# untitled.net
KiCad netlist of a schematic drawn in EAGLE
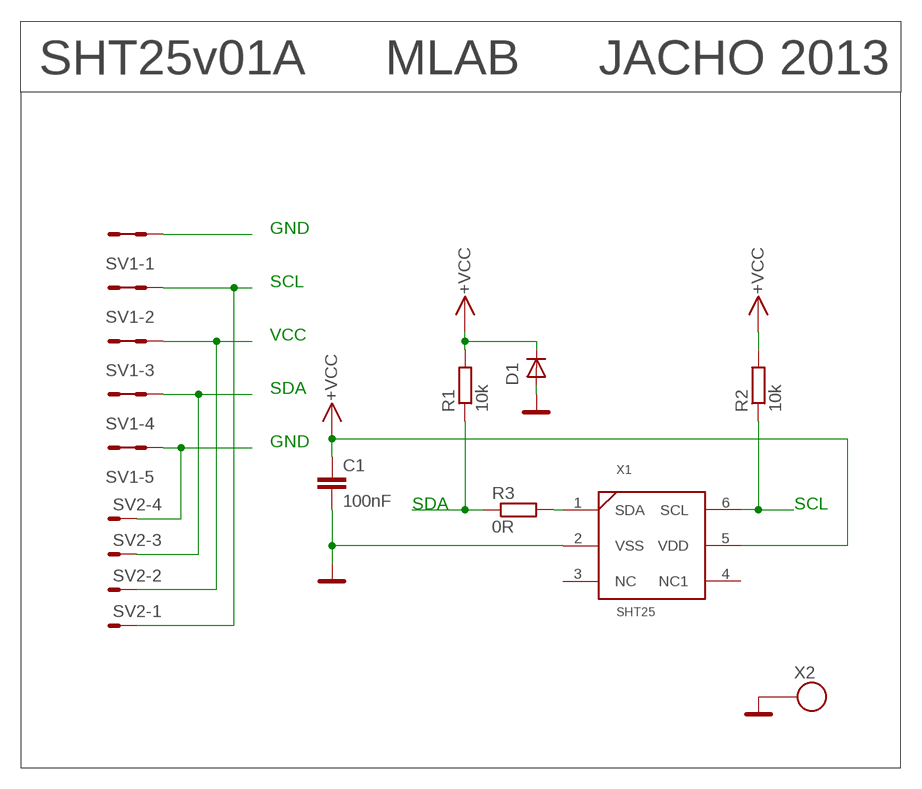
[diagram p0: schematic, sheet 1]

(export (version "E")
  (design (tool "Eeschema 10.0.6"))
  (components
    (comp (ref "C1")
      (value "100nF")
      (footprint "eagle-import:C0805")
      (libsource (lib "eagle-import") (part "C-EUC0805"))
    )
    (comp (ref "D1")
      (value "D-OB.SMA")
      (footprint "eagle-import:SMA")
      (libsource (lib "eagle-import") (part "D-OB.SMA"))
    )
    (comp (ref "R1")
      (value "10k")
      (footprint "eagle-import:R0805")
      (libsource (lib "eagle-import") (part "R-EU_R0805"))
    )
    (comp (ref "R2")
      (value "10k")
      (footprint "eagle-import:R0805")
      (libsource (lib "eagle-import") (part "R-EU_R0805"))
    )
    (comp (ref "R3")
      (value "0R")
      (footprint "eagle-import:R0805")
      (libsource (lib "eagle-import") (part "R-EU_R0805"))
    )
    (comp (ref "SV1")
      (value "MA05-2")
      (footprint "eagle-import:MA05-2")
      (libsource (lib "eagle-import") (part "MA05-2"))
    )
    (comp (ref "SV2")
      (value "SMD_MA04-01")
      (footprint "eagle-import:SMD_MA04-1")
      (libsource (lib "eagle-import") (part "SMD_MA04-01"))
    )
    (comp (ref "X1")
      (value "SHT25")
      (footprint "eagle-import:SHT25")
      (libsource (lib "eagle-import") (part "SHT25"))
    )
    (comp (ref "X2")
      (value "SROUB3M")
      (footprint "eagle-import:SROUB3M")
      (libsource (lib "eagle-import") (part "SROUB3M"))
    )
  )
  (nets
    (net (code "1") (name "+VCC") (class "Default")
      (node (ref "C1") (pin "1") (pinfunction "1_1") (pintype "passive"))
      (node (ref "D1") (pin "K") (pinfunction "C_K") (pintype "passive"))
      (node (ref "R1") (pin "2") (pinfunction "2_2") (pintype "passive"))
      (node (ref "R2") (pin "2") (pinfunction "2_2") (pintype "passive"))
      (node (ref "SV1") (pin "5") (pinfunction "K_5") (pintype "passive"))
      (node (ref "SV1") (pin "6") (pinfunction "K_6") (pintype "passive"))
      (node (ref "SV2") (pin "2") (pinfunction "P$1_2") (pintype "passive"))
      (node (ref "X1") (pin "5") (pinfunction "VDD_5") (pintype "bidirectional"))
    )
    (net (code "2") (name "/SCL") (class "Default")
      (node (ref "R2") (pin "1") (pinfunction "1_1") (pintype "passive"))
      (node (ref "SV1") (pin "3") (pinfunction "K_3") (pintype "passive"))
      (node (ref "SV1") (pin "4") (pinfunction "K_4") (pintype "passive"))
      (node (ref "SV2") (pin "1") (pinfunction "P$1_1") (pintype "passive"))
      (node (ref "X1") (pin "6") (pinfunction "SCL_6") (pintype "bidirectional"))
    )
    (net (code "3") (name "/SDA") (class "Default")
      (node (ref "R1") (pin "1") (pinfunction "1_1") (pintype "passive"))
      (node (ref "R3") (pin "1") (pinfunction "1_1") (pintype "passive"))
      (node (ref "SV1") (pin "7") (pinfunction "K_7") (pintype "passive"))
      (node (ref "SV1") (pin "8") (pinfunction "K_8") (pintype "passive"))
      (node (ref "SV2") (pin "3") (pinfunction "P$1_3") (pintype "passive"))
    )
    (net (code "4") (name "GND") (class "Default")
      (node (ref "C1") (pin "2") (pinfunction "2_2") (pintype "passive"))
      (node (ref "D1") (pin "A") (pinfunction "A_A") (pintype "passive"))
      (node (ref "SV1") (pin "1") (pinfunction "K_1") (pintype "passive"))
      (node (ref "SV1") (pin "10") (pinfunction "K_10") (pintype "passive"))
      (node (ref "SV1") (pin "2") (pinfunction "K_2") (pintype "passive"))
      (node (ref "SV1") (pin "9") (pinfunction "K_9") (pintype "passive"))
      (node (ref "SV2") (pin "4") (pinfunction "P$1_4") (pintype "passive"))
      (node (ref "X1") (pin "2") (pinfunction "VSS_2") (pintype "bidirectional"))
      (node (ref "X2") (pin "P$1") (pinfunction "P$1_P$1") (pintype "bidirectional"))
    )
    (net (code "5") (name "Net-(X1-SDA)") (class "Default")
      (node (ref "R3") (pin "2") (pinfunction "2_2") (pintype "passive"))
      (node (ref "X1") (pin "1") (pinfunction "SDA_1") (pintype "bidirectional"))
    )
    (net (code "6") (name "unconnected-(X1-NC-Pad3)") (class "Default")
      (node (ref "X1") (pin "3") (pinfunction "NC_3") (pintype "bidirectional"))
    )
    (net (code "7") (name "unconnected-(X1-NC1-Pad4)") (class "Default")
      (node (ref "X1") (pin "4") (pinfunction "NC1_4") (pintype "bidirectional"))
    )
  )
)
